# CAN-FD.net
KiCad netlist of a schematic drawn in Altium Designer
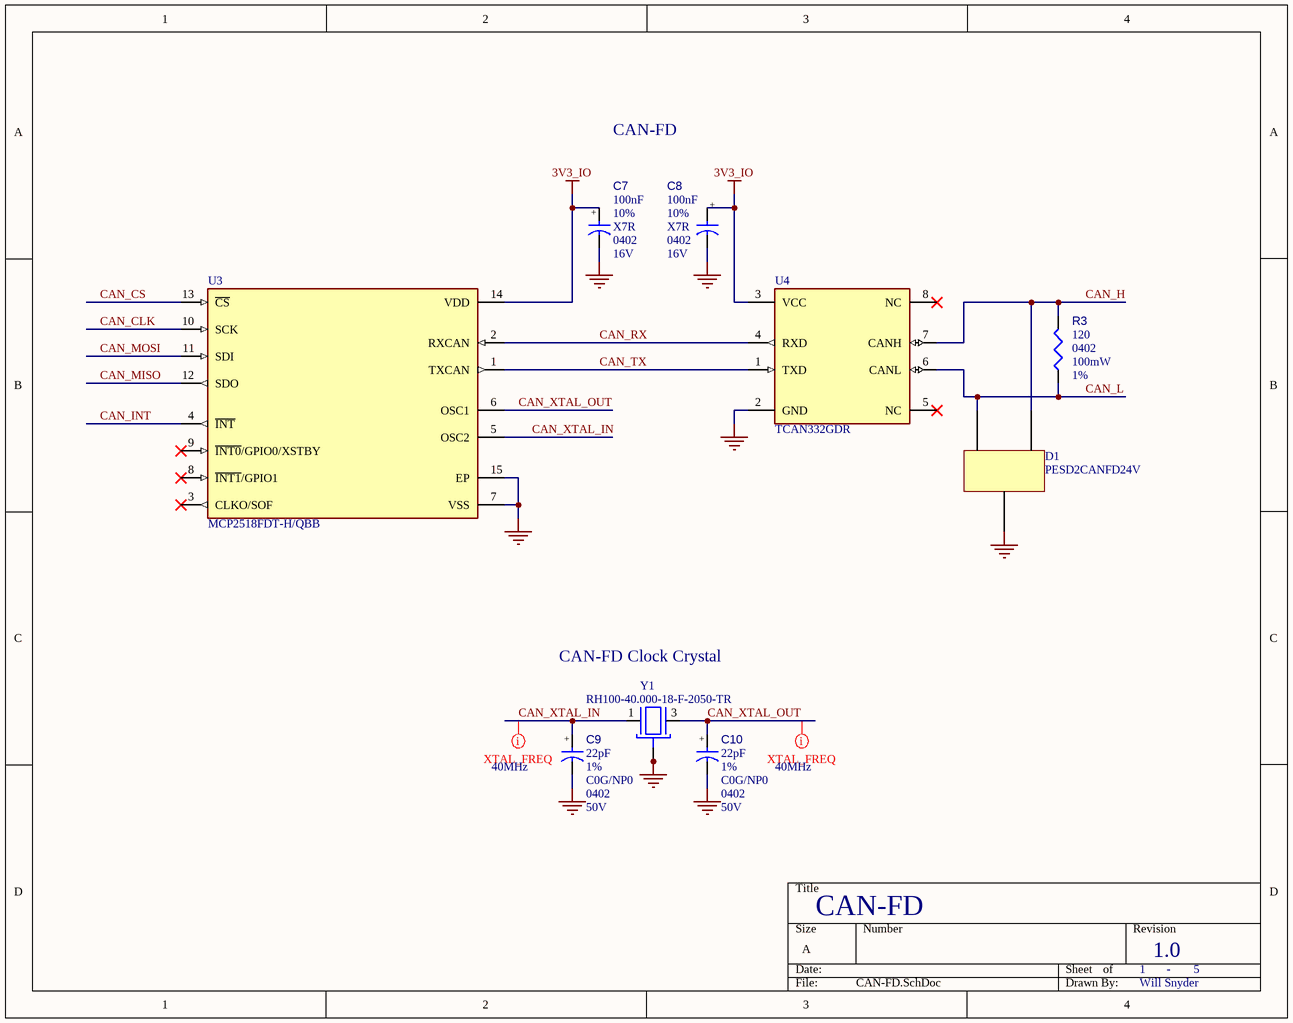
[diagram p0: CAN-FD.SchDoc]

(export (version "E")
  (design (tool "Eeschema 10.0.6"))
  (components
    (comp (ref "C7")
      (value "100nF")
      (footprint "CAPC1005X56X25LL10T15")
      (description "Chip Capacitor, 0.1 uF, +/- 5%, 16 V, 0402 (1005 Metric)")
      (fields
        (field (name "TOLERANCE") "10%")
        (field (name "CAPACITOR TYPE") "X7R")
        (field (name "CASE/PACKAGE") "0402")
        (field (name "VOLTAGE RATING") "16V")
        (field (name "Comment") "Capacitor 0.1 uF +/- 5% 16 V 0402")
      )
      (libsource (lib "Personal Workspace") (part "CAP-NP-2"))
    )
    (comp (ref "C8")
      (value "100nF")
      (footprint "CAPC1005X56X25LL10T15")
      (description "Chip Capacitor, 0.1 uF, +/- 5%, 16 V, 0402 (1005 Metric)")
      (fields
        (field (name "TOLERANCE") "10%")
        (field (name "CAPACITOR TYPE") "X7R")
        (field (name "CASE/PACKAGE") "0402")
        (field (name "VOLTAGE RATING") "16V")
        (field (name "Comment") "Capacitor 0.1 uF +/- 5% 16 V 0402")
      )
      (libsource (lib "") (part "CAP-NP-2_1"))
    )
    (comp (ref "C9")
      (value "22pF")
      (footprint "CAPC1005X56X25LL10T15")
      (description "Chip Capacitor, 0.1 uF, +/- 5%, 16 V, 0402 (1005 Metric)")
      (fields
        (field (name "TOLERANCE") "1%")
        (field (name "CAPACITOR TYPE") "C0G/NP0")
        (field (name "CASE/PACKAGE") "0402")
        (field (name "VOLTAGE RATING") "50V")
        (field (name "Comment") "Capacitor 0.1 uF +/- 5% 16 V 0402")
      )
      (libsource (lib "Personal Workspace") (part "CAP-NP-2"))
    )
    (comp (ref "C10")
      (value "22pF")
      (footprint "CAPC1005X56X25LL10T15")
      (description "Chip Capacitor, 0.1 uF, +/- 5%, 16 V, 0402 (1005 Metric)")
      (fields
        (field (name "TOLERANCE") "1%")
        (field (name "CAPACITOR TYPE") "C0G/NP0")
        (field (name "CASE/PACKAGE") "0402")
        (field (name "VOLTAGE RATING") "50V")
        (field (name "Comment") "Capacitor 0.1 uF +/- 5% 16 V 0402")
      )
      (libsource (lib "Personal Workspace") (part "CAP-NP-2"))
    )
    (comp (ref "D1")
      (value "PESD2CANFD24V")
      (footprint "SOT95P230X110-3N")
      (description "Trans Voltage Suppressor Diode, 24V V(RWM), Bidirectional, 2 Element, Silicon, TO-236AB")
      (libsource (lib "Personal Workspace") (part "PESD2CANFD24V-TR"))
    )
    (comp (ref "R3")
      (value "120")
      (footprint "FP-ERJ2RK-IPC_B")
      (fields
        (field (name "CASE/PACKAGE") "0402")
        (field (name "POWER") "100mW")
        (field (name "TOLERANCE") "1%")
        (field (name "Comment") "ERJ-2RKF3002X")
      )
      (libsource (lib "Personal Workspace") (part "RES-2"))
    )
    (comp (ref "U3")
      (value "MCP2518FDT-H/QBB")
      (footprint "FP-C04-21361-IPC_A")
      (description "1 Channel(s), 8MBps, CMOS, PDCC14")
      (libsource (lib "Personal Workspace") (part "171200ff88dd600c7d3e4b98ff00d41"))
    )
    (comp (ref "U4")
      (value "TCAN332GDR")
      (footprint "Copy of SOIC127P599X175-8N")
      (description "Interface Circuit, PDSO8")
      (libsource (lib "Personal Workspace") (part "TCAN332GDR"))
    )
    (comp (ref "Y1")
      (value "RH100-40.000-18-F-2050-TR")
      (footprint "XTAL_RH100-40.000-18-F-2050-TR")
      (description "40 MHz Â±20ppm Crystal 18pF 50 Ohms 4-SMD, No Lead")
      (fields (field (name "MF") "Raltron Electronics"))
      (libsource (lib "Personal Workspace") (part "RH100-40.000-18-F-2050-TR"))
    )
  )
  (nets
    (net (code "1") (name "/CAN_CLK") (class "Default")
      (node (ref "U3") (pin "10") (pinfunction "SCK_10") (pintype "input"))
    )
    (net (code "2") (name "/CAN_CS") (class "Default")
      (node (ref "U3") (pin "13") (pinfunction "~{CS}_13") (pintype "input"))
    )
    (net (code "3") (name "/CAN_H") (class "Default")
      (node (ref "D1") (pin "1") (pinfunction "K1_1") (pintype "passive"))
      (node (ref "R3") (pin "1") (pinfunction "1_1") (pintype "passive"))
      (node (ref "U4") (pin "7") (pinfunction "CANH_7") (pintype "bidirectional"))
    )
    (net (code "4") (name "/CAN_INT") (class "Default")
      (node (ref "U3") (pin "4") (pinfunction "~{INT}_4") (pintype "output"))
    )
    (net (code "5") (name "/CAN_L") (class "Default")
      (node (ref "D1") (pin "2") (pinfunction "K2_2") (pintype "passive"))
      (node (ref "R3") (pin "2") (pinfunction "2_2") (pintype "passive"))
      (node (ref "U4") (pin "6") (pinfunction "CANL_6") (pintype "bidirectional"))
    )
    (net (code "6") (name "/CAN_MISO") (class "Default")
      (node (ref "U3") (pin "12") (pinfunction "SDO_12") (pintype "output"))
    )
    (net (code "7") (name "/CAN_MOSI") (class "Default")
      (node (ref "U3") (pin "11") (pinfunction "SDI_11") (pintype "input"))
    )
    (net (code "8") (name "/CAN_RX") (class "Default")
      (node (ref "U3") (pin "2") (pinfunction "RXCAN_2") (pintype "input"))
      (node (ref "U4") (pin "4") (pinfunction "RXD_4") (pintype "output"))
    )
    (net (code "9") (name "/CAN_TX") (class "Default")
      (node (ref "U3") (pin "1") (pinfunction "TXCAN_1") (pintype "output"))
      (node (ref "U4") (pin "1") (pinfunction "TXD_1") (pintype "input"))
    )
    (net (code "10") (name "/CAN_XTAL_IN") (class "Default")
      (node (ref "C9") (pin "1") (pinfunction "1_1") (pintype "passive"))
      (node (ref "U3") (pin "5") (pinfunction "OSC2_5") (pintype "passive"))
      (node (ref "Y1") (pin "1") (pinfunction "1_1") (pintype "passive"))
    )
    (net (code "11") (name "/CAN_XTAL_OUT") (class "Default")
      (node (ref "C10") (pin "1") (pinfunction "1_1") (pintype "passive"))
      (node (ref "U3") (pin "6") (pinfunction "OSC1_6") (pintype "passive"))
      (node (ref "Y1") (pin "3") (pinfunction "3_3") (pintype "passive"))
    )
    (net (code "12") (name "3V3_IO") (class "Default")
      (node (ref "C7") (pin "1") (pinfunction "1_1") (pintype "passive"))
      (node (ref "C8") (pin "1") (pinfunction "1_1") (pintype "passive"))
      (node (ref "U3") (pin "14") (pinfunction "VDD_14") (pintype "power_in"))
      (node (ref "U4") (pin "3") (pinfunction "VCC_3") (pintype "power_in"))
    )
    (net (code "13") (name "GND") (class "Default")
      (node (ref "C10") (pin "2") (pinfunction "2_2") (pintype "passive"))
      (node (ref "C7") (pin "2") (pinfunction "2_2") (pintype "passive"))
      (node (ref "C8") (pin "2") (pinfunction "2_2") (pintype "passive"))
      (node (ref "C9") (pin "2") (pinfunction "2_2") (pintype "passive"))
      (node (ref "D1") (pin "3") (pinfunction "CC_3") (pintype "passive"))
      (node (ref "U3") (pin "15") (pinfunction "EP_15") (pintype "power_in"))
      (node (ref "U3") (pin "7") (pinfunction "VSS_7") (pintype "power_in"))
      (node (ref "U4") (pin "2") (pinfunction "GND_2") (pintype "power_in"))
      (node (ref "Y1") (pin "2") (pinfunction "GND_2") (pintype "power_in"))
      (node (ref "Y1") (pin "4") (pinfunction "GND_4") (pintype "power_in"))
    )
    (net (code "14") (name "unconnected-(U3-CLKO{slash}SOF-Pad3)") (class "Default")
      (node (ref "U3") (pin "3") (pinfunction "CLKO/SOF_3") (pintype "output+no_connect"))
    )
    (net (code "15") (name "unconnected-(U3-~{INT0}{slash}GPIO0{slash}XSTBY-Pad9)") (class "Default")
      (node (ref "U3") (pin "9") (pinfunction "~{INT0}/GPIO0/XSTBY_9") (pintype "input+no_connect"))
    )
    (net (code "16") (name "unconnected-(U3-~{INT1}{slash}GPIO1-Pad8)") (class "Default")
      (node (ref "U3") (pin "8") (pinfunction "~{INT1}/GPIO1_8") (pintype "input+no_connect"))
    )
    (net (code "17") (name "unconnected-(U4-NC-Pad5)") (class "Default")
      (node (ref "U4") (pin "5") (pinfunction "NC_5") (pintype "passive+no_connect"))
    )
    (net (code "18") (name "unconnected-(U4-NC-Pad8)") (class "Default")
      (node (ref "U4") (pin "8") (pinfunction "NC_8") (pintype "passive+no_connect"))
    )
  )
)
